# VoltageHeaders.net
KiCad netlist of a schematic drawn in Altium Designer
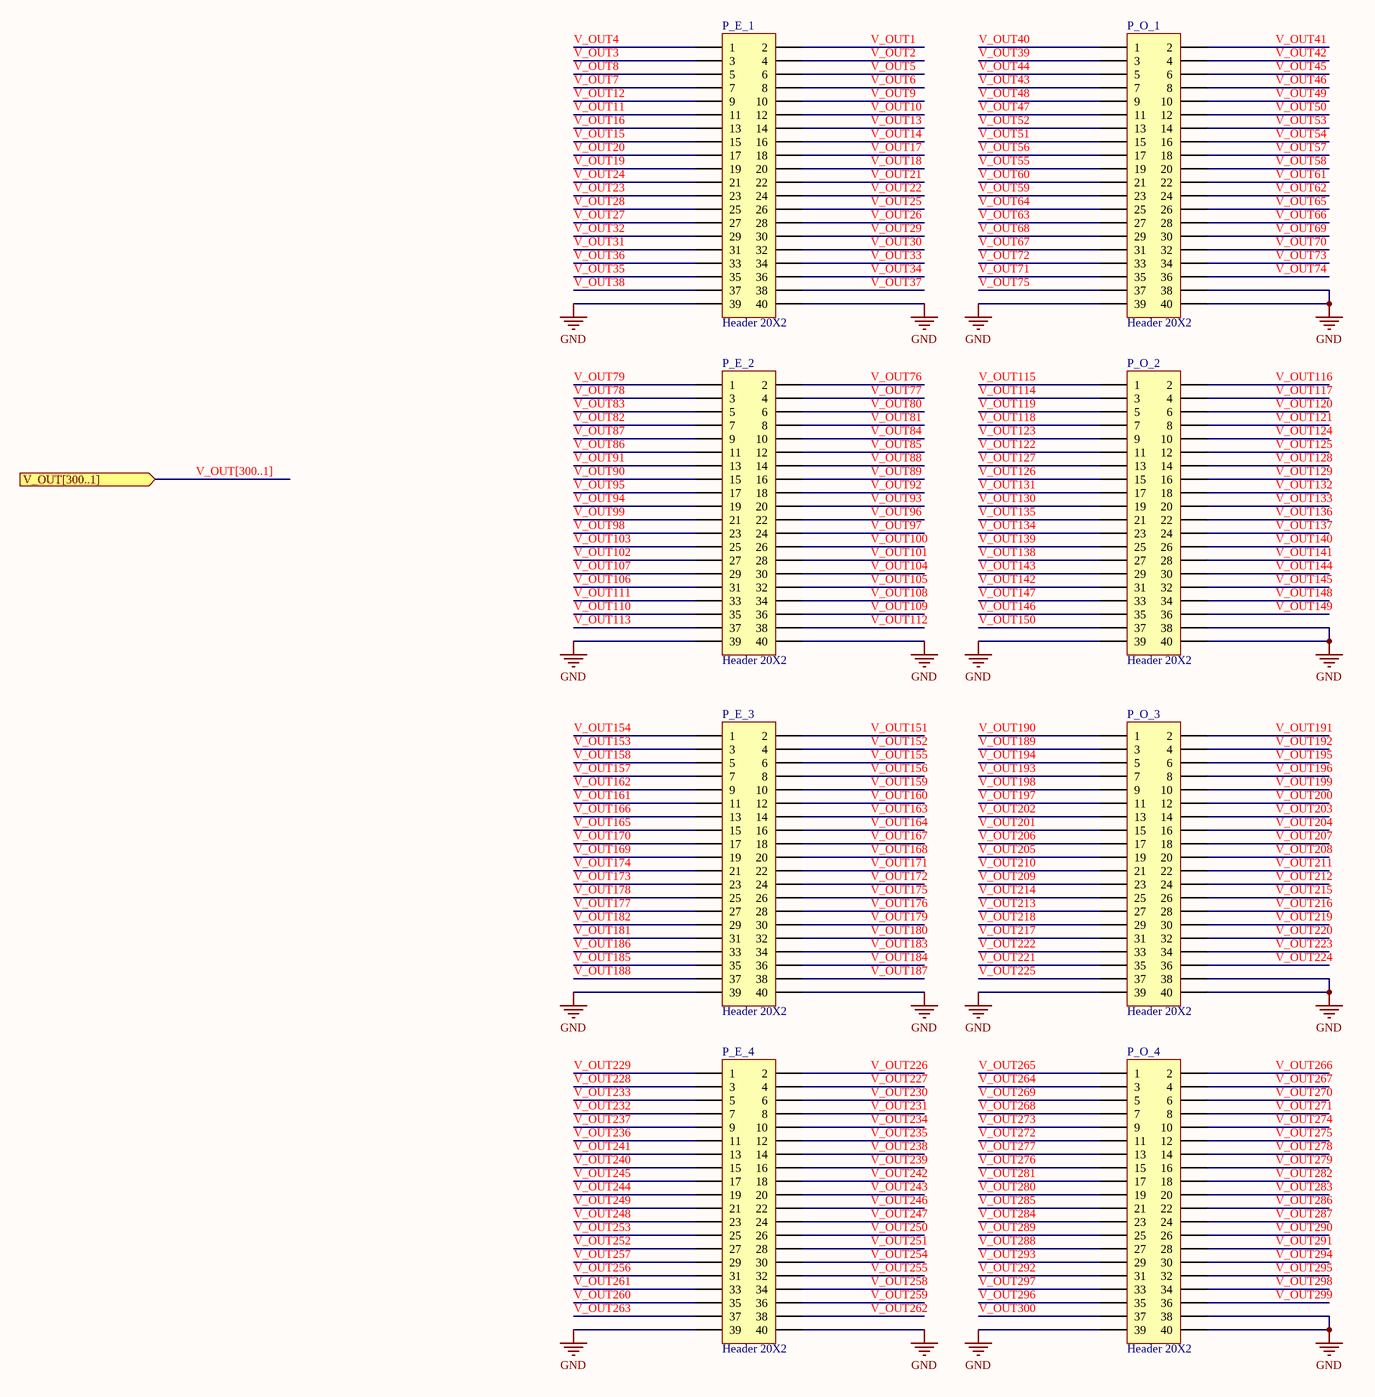
[diagram p0: VoltageHeaders.SchDoc]

(export (version "E")
  (design (tool "Eeschema 10.0.6"))
  (components
    (comp (ref "P_E_1")
      (value "Header 20X2")
      (footprint "HDR2X20")
      (description "Headers & Wire Housings 2X20 POS VERT TIN")
      (fields (field (name "MFR") "TE Connectivity / AMP") (field (name "MFR PART NO") "2-826942-0"))
      (libsource (lib "Miscellaneous Connectors") (part "Header 20X2"))
    )
    (comp (ref "P_E_2")
      (value "Header 20X2")
      (footprint "HDR2X20")
      (description "Headers & Wire Housings 2X20 POS VERT TIN")
      (fields (field (name "MFR") "TE Connectivity / AMP") (field (name "MFR PART NO") "2-826942-0"))
      (libsource (lib "Miscellaneous Connectors") (part "Header 20X2"))
    )
    (comp (ref "P_E_3")
      (value "Header 20X2")
      (footprint "HDR2X20")
      (description "Headers & Wire Housings 2X20 POS VERT TIN")
      (fields (field (name "MFR") "TE Connectivity / AMP") (field (name "MFR PART NO") "2-826942-0"))
      (libsource (lib "Miscellaneous Connectors") (part "Header 20X2"))
    )
    (comp (ref "P_E_4")
      (value "Header 20X2")
      (footprint "HDR2X20")
      (description "Headers & Wire Housings 2X20 POS VERT TIN")
      (fields (field (name "MFR") "TE Connectivity / AMP") (field (name "MFR PART NO") "2-826942-0"))
      (libsource (lib "Miscellaneous Connectors") (part "Header 20X2"))
    )
    (comp (ref "P_O_1")
      (value "Header 20X2")
      (footprint "HDR2X20")
      (description "Headers & Wire Housings 2X20 POS VERT TIN")
      (fields (field (name "MFR") "TE Connectivity / AMP") (field (name "MFR PART NO") "2-826942-0"))
      (libsource (lib "Miscellaneous Connectors") (part "Header 20X2"))
    )
    (comp (ref "P_O_2")
      (value "Header 20X2")
      (footprint "HDR2X20")
      (description "Headers & Wire Housings 2X20 POS VERT TIN")
      (fields (field (name "MFR") "TE Connectivity / AMP") (field (name "MFR PART NO") "2-826942-0"))
      (libsource (lib "Miscellaneous Connectors") (part "Header 20X2"))
    )
    (comp (ref "P_O_3")
      (value "Header 20X2")
      (footprint "HDR2X20")
      (description "Headers & Wire Housings 2X20 POS VERT TIN")
      (fields (field (name "MFR") "TE Connectivity / AMP") (field (name "MFR PART NO") "2-826942-0"))
      (libsource (lib "Miscellaneous Connectors") (part "Header 20X2"))
    )
    (comp (ref "P_O_4")
      (value "Header 20X2")
      (footprint "HDR2X20")
      (description "Headers & Wire Housings 2X20 POS VERT TIN")
      (fields (field (name "MFR") "TE Connectivity / AMP") (field (name "MFR PART NO") "2-826942-0"))
      (libsource (lib "Miscellaneous Connectors") (part "Header 20X2"))
    )
  )
  (nets
    (net (code "1") (name "/V_OUT1") (class "Default")
      (node (ref "P_E_1") (pin "2") (pinfunction "2_2") (pintype "passive"))
    )
    (net (code "2") (name "/V_OUT2") (class "Default")
      (node (ref "P_E_1") (pin "4") (pinfunction "4_4") (pintype "passive"))
    )
    (net (code "3") (name "/V_OUT3") (class "Default")
      (node (ref "P_E_1") (pin "3") (pinfunction "3_3") (pintype "passive"))
    )
    (net (code "4") (name "/V_OUT4") (class "Default")
      (node (ref "P_E_1") (pin "1") (pinfunction "1_1") (pintype "passive"))
    )
    (net (code "5") (name "/V_OUT5") (class "Default")
      (node (ref "P_E_1") (pin "6") (pinfunction "6_6") (pintype "passive"))
    )
    (net (code "6") (name "/V_OUT6") (class "Default")
      (node (ref "P_E_1") (pin "8") (pinfunction "8_8") (pintype "passive"))
    )
    (net (code "7") (name "/V_OUT7") (class "Default")
      (node (ref "P_E_1") (pin "7") (pinfunction "7_7") (pintype "passive"))
    )
    (net (code "8") (name "/V_OUT8") (class "Default")
      (node (ref "P_E_1") (pin "5") (pinfunction "5_5") (pintype "passive"))
    )
    (net (code "9") (name "/V_OUT9") (class "Default")
      (node (ref "P_E_1") (pin "10") (pinfunction "10_10") (pintype "passive"))
    )
    (net (code "10") (name "/V_OUT10") (class "Default")
      (node (ref "P_E_1") (pin "12") (pinfunction "12_12") (pintype "passive"))
    )
    (net (code "11") (name "/V_OUT11") (class "Default")
      (node (ref "P_E_1") (pin "11") (pinfunction "11_11") (pintype "passive"))
    )
    (net (code "12") (name "/V_OUT12") (class "Default")
      (node (ref "P_E_1") (pin "9") (pinfunction "9_9") (pintype "passive"))
    )
    (net (code "13") (name "/V_OUT13") (class "Default")
      (node (ref "P_E_1") (pin "14") (pinfunction "14_14") (pintype "passive"))
    )
    (net (code "14") (name "/V_OUT14") (class "Default")
      (node (ref "P_E_1") (pin "16") (pinfunction "16_16") (pintype "passive"))
    )
    (net (code "15") (name "/V_OUT15") (class "Default")
      (node (ref "P_E_1") (pin "15") (pinfunction "15_15") (pintype "passive"))
    )
    (net (code "16") (name "/V_OUT16") (class "Default")
      (node (ref "P_E_1") (pin "13") (pinfunction "13_13") (pintype "passive"))
    )
    (net (code "17") (name "/V_OUT17") (class "Default")
      (node (ref "P_E_1") (pin "18") (pinfunction "18_18") (pintype "passive"))
    )
    (net (code "18") (name "/V_OUT18") (class "Default")
      (node (ref "P_E_1") (pin "20") (pinfunction "20_20") (pintype "passive"))
    )
    (net (code "19") (name "/V_OUT19") (class "Default")
      (node (ref "P_E_1") (pin "19") (pinfunction "19_19") (pintype "passive"))
    )
    (net (code "20") (name "/V_OUT20") (class "Default")
      (node (ref "P_E_1") (pin "17") (pinfunction "17_17") (pintype "passive"))
    )
    (net (code "21") (name "/V_OUT21") (class "Default")
      (node (ref "P_E_1") (pin "22") (pinfunction "22_22") (pintype "passive"))
    )
    (net (code "22") (name "/V_OUT22") (class "Default")
      (node (ref "P_E_1") (pin "24") (pinfunction "24_24") (pintype "passive"))
    )
    (net (code "23") (name "/V_OUT23") (class "Default")
      (node (ref "P_E_1") (pin "23") (pinfunction "23_23") (pintype "passive"))
    )
    (net (code "24") (name "/V_OUT24") (class "Default")
      (node (ref "P_E_1") (pin "21") (pinfunction "21_21") (pintype "passive"))
    )
    (net (code "25") (name "/V_OUT25") (class "Default")
      (node (ref "P_E_1") (pin "26") (pinfunction "26_26") (pintype "passive"))
    )
    (net (code "26") (name "/V_OUT26") (class "Default")
      (node (ref "P_E_1") (pin "28") (pinfunction "28_28") (pintype "passive"))
    )
    (net (code "27") (name "/V_OUT27") (class "Default")
      (node (ref "P_E_1") (pin "27") (pinfunction "27_27") (pintype "passive"))
    )
    (net (code "28") (name "/V_OUT28") (class "Default")
      (node (ref "P_E_1") (pin "25") (pinfunction "25_25") (pintype "passive"))
    )
    (net (code "29") (name "/V_OUT29") (class "Default")
      (node (ref "P_E_1") (pin "30") (pinfunction "30_30") (pintype "passive"))
    )
    (net (code "30") (name "/V_OUT30") (class "Default")
      (node (ref "P_E_1") (pin "32") (pinfunction "32_32") (pintype "passive"))
    )
    (net (code "31") (name "/V_OUT31") (class "Default")
      (node (ref "P_E_1") (pin "31") (pinfunction "31_31") (pintype "passive"))
    )
    (net (code "32") (name "/V_OUT32") (class "Default")
      (node (ref "P_E_1") (pin "29") (pinfunction "29_29") (pintype "passive"))
    )
    (net (code "33") (name "/V_OUT33") (class "Default")
      (node (ref "P_E_1") (pin "34") (pinfunction "34_34") (pintype "passive"))
    )
    (net (code "34") (name "/V_OUT34") (class "Default")
      (node (ref "P_E_1") (pin "36") (pinfunction "36_36") (pintype "passive"))
    )
    (net (code "35") (name "/V_OUT35") (class "Default")
      (node (ref "P_E_1") (pin "35") (pinfunction "35_35") (pintype "passive"))
    )
    (net (code "36") (name "/V_OUT36") (class "Default")
      (node (ref "P_E_1") (pin "33") (pinfunction "33_33") (pintype "passive"))
    )
    (net (code "37") (name "/V_OUT37") (class "Default")
      (node (ref "P_E_1") (pin "38") (pinfunction "38_38") (pintype "passive"))
    )
    (net (code "38") (name "/V_OUT38") (class "Default")
      (node (ref "P_E_1") (pin "37") (pinfunction "37_37") (pintype "passive"))
    )
    (net (code "39") (name "/V_OUT39") (class "Default")
      (node (ref "P_O_1") (pin "3") (pinfunction "3_3") (pintype "passive"))
    )
    (net (code "40") (name "/V_OUT40") (class "Default")
      (node (ref "P_O_1") (pin "1") (pinfunction "1_1") (pintype "passive"))
    )
    (net (code "41") (name "/V_OUT41") (class "Default")
      (node (ref "P_O_1") (pin "2") (pinfunction "2_2") (pintype "passive"))
    )
    (net (code "42") (name "/V_OUT42") (class "Default")
      (node (ref "P_O_1") (pin "4") (pinfunction "4_4") (pintype "passive"))
    )
    (net (code "43") (name "/V_OUT43") (class "Default")
      (node (ref "P_O_1") (pin "7") (pinfunction "7_7") (pintype "passive"))
    )
    (net (code "44") (name "/V_OUT44") (class "Default")
      (node (ref "P_O_1") (pin "5") (pinfunction "5_5") (pintype "passive"))
    )
    (net (code "45") (name "/V_OUT45") (class "Default")
      (node (ref "P_O_1") (pin "6") (pinfunction "6_6") (pintype "passive"))
    )
    (net (code "46") (name "/V_OUT46") (class "Default")
      (node (ref "P_O_1") (pin "8") (pinfunction "8_8") (pintype "passive"))
    )
    (net (code "47") (name "/V_OUT47") (class "Default")
      (node (ref "P_O_1") (pin "11") (pinfunction "11_11") (pintype "passive"))
    )
    (net (code "48") (name "/V_OUT48") (class "Default")
      (node (ref "P_O_1") (pin "9") (pinfunction "9_9") (pintype "passive"))
    )
    (net (code "49") (name "/V_OUT49") (class "Default")
      (node (ref "P_O_1") (pin "10") (pinfunction "10_10") (pintype "passive"))
    )
    (net (code "50") (name "/V_OUT50") (class "Default")
      (node (ref "P_O_1") (pin "12") (pinfunction "12_12") (pintype "passive"))
    )
    (net (code "51") (name "/V_OUT51") (class "Default")
      (node (ref "P_O_1") (pin "15") (pinfunction "15_15") (pintype "passive"))
    )
    (net (code "52") (name "/V_OUT52") (class "Default")
      (node (ref "P_O_1") (pin "13") (pinfunction "13_13") (pintype "passive"))
    )
    (net (code "53") (name "/V_OUT53") (class "Default")
      (node (ref "P_O_1") (pin "14") (pinfunction "14_14") (pintype "passive"))
    )
    (net (code "54") (name "/V_OUT54") (class "Default")
      (node (ref "P_O_1") (pin "16") (pinfunction "16_16") (pintype "passive"))
    )
    (net (code "55") (name "/V_OUT55") (class "Default")
      (node (ref "P_O_1") (pin "19") (pinfunction "19_19") (pintype "passive"))
    )
    (net (code "56") (name "/V_OUT56") (class "Default")
      (node (ref "P_O_1") (pin "17") (pinfunction "17_17") (pintype "passive"))
    )
    (net (code "57") (name "/V_OUT57") (class "Default")
      (node (ref "P_O_1") (pin "18") (pinfunction "18_18") (pintype "passive"))
    )
    (net (code "58") (name "/V_OUT58") (class "Default")
      (node (ref "P_O_1") (pin "20") (pinfunction "20_20") (pintype "passive"))
    )
    (net (code "59") (name "/V_OUT59") (class "Default")
      (node (ref "P_O_1") (pin "23") (pinfunction "23_23") (pintype "passive"))
    )
    (net (code "60") (name "/V_OUT60") (class "Default")
      (node (ref "P_O_1") (pin "21") (pinfunction "21_21") (pintype "passive"))
    )
    (net (code "61") (name "/V_OUT61") (class "Default")
      (node (ref "P_O_1") (pin "22") (pinfunction "22_22") (pintype "passive"))
    )
    (net (code "62") (name "/V_OUT62") (class "Default")
      (node (ref "P_O_1") (pin "24") (pinfunction "24_24") (pintype "passive"))
    )
    (net (code "63") (name "/V_OUT63") (class "Default")
      (node (ref "P_O_1") (pin "27") (pinfunction "27_27") (pintype "passive"))
    )
    (net (code "64") (name "/V_OUT64") (class "Default")
      (node (ref "P_O_1") (pin "25") (pinfunction "25_25") (pintype "passive"))
    )
    (net (code "65") (name "/V_OUT65") (class "Default")
      (node (ref "P_O_1") (pin "26") (pinfunction "26_26") (pintype "passive"))
    )
    (net (code "66") (name "/V_OUT66") (class "Default")
      (node (ref "P_O_1") (pin "28") (pinfunction "28_28") (pintype "passive"))
    )
    (net (code "67") (name "/V_OUT67") (class "Default")
      (node (ref "P_O_1") (pin "31") (pinfunction "31_31") (pintype "passive"))
    )
    (net (code "68") (name "/V_OUT68") (class "Default")
      (node (ref "P_O_1") (pin "29") (pinfunction "29_29") (pintype "passive"))
    )
    (net (code "69") (name "/V_OUT69") (class "Default")
      (node (ref "P_O_1") (pin "30") (pinfunction "30_30") (pintype "passive"))
    )
    (net (code "70") (name "/V_OUT70") (class "Default")
      (node (ref "P_O_1") (pin "32") (pinfunction "32_32") (pintype "passive"))
    )
    (net (code "71") (name "/V_OUT71") (class "Default")
      (node (ref "P_O_1") (pin "35") (pinfunction "35_35") (pintype "passive"))
    )
    (net (code "72") (name "/V_OUT72") (class "Default")
      (node (ref "P_O_1") (pin "33") (pinfunction "33_33") (pintype "passive"))
    )
    (net (code "73") (name "/V_OUT73") (class "Default")
      (node (ref "P_O_1") (pin "34") (pinfunction "34_34") (pintype "passive"))
    )
    (net (code "74") (name "/V_OUT74") (class "Default")
      (node (ref "P_O_1") (pin "36") (pinfunction "36_36") (pintype "passive"))
    )
    (net (code "75") (name "/V_OUT75") (class "Default")
      (node (ref "P_O_1") (pin "37") (pinfunction "37_37") (pintype "passive"))
    )
    (net (code "76") (name "/V_OUT76") (class "Default")
      (node (ref "P_E_2") (pin "2") (pinfunction "2_2") (pintype "passive"))
    )
    (net (code "77") (name "/V_OUT77") (class "Default")
      (node (ref "P_E_2") (pin "4") (pinfunction "4_4") (pintype "passive"))
    )
    (net (code "78") (name "/V_OUT78") (class "Default")
      (node (ref "P_E_2") (pin "3") (pinfunction "3_3") (pintype "passive"))
    )
    (net (code "79") (name "/V_OUT79") (class "Default")
      (node (ref "P_E_2") (pin "1") (pinfunction "1_1") (pintype "passive"))
    )
    (net (code "80") (name "/V_OUT80") (class "Default")
      (node (ref "P_E_2") (pin "6") (pinfunction "6_6") (pintype "passive"))
    )
    (net (code "81") (name "/V_OUT81") (class "Default")
      (node (ref "P_E_2") (pin "8") (pinfunction "8_8") (pintype "passive"))
    )
    (net (code "82") (name "/V_OUT82") (class "Default")
      (node (ref "P_E_2") (pin "7") (pinfunction "7_7") (pintype "passive"))
    )
    (net (code "83") (name "/V_OUT83") (class "Default")
      (node (ref "P_E_2") (pin "5") (pinfunction "5_5") (pintype "passive"))
    )
    (net (code "84") (name "/V_OUT84") (class "Default")
      (node (ref "P_E_2") (pin "10") (pinfunction "10_10") (pintype "passive"))
    )
    (net (code "85") (name "/V_OUT85") (class "Default")
      (node (ref "P_E_2") (pin "12") (pinfunction "12_12") (pintype "passive"))
    )
    (net (code "86") (name "/V_OUT86") (class "Default")
      (node (ref "P_E_2") (pin "11") (pinfunction "11_11") (pintype "passive"))
    )
    (net (code "87") (name "/V_OUT87") (class "Default")
      (node (ref "P_E_2") (pin "9") (pinfunction "9_9") (pintype "passive"))
    )
    (net (code "88") (name "/V_OUT88") (class "Default")
      (node (ref "P_E_2") (pin "14") (pinfunction "14_14") (pintype "passive"))
    )
    (net (code "89") (name "/V_OUT89") (class "Default")
      (node (ref "P_E_2") (pin "16") (pinfunction "16_16") (pintype "passive"))
    )
    (net (code "90") (name "/V_OUT90") (class "Default")
      (node (ref "P_E_2") (pin "15") (pinfunction "15_15") (pintype "passive"))
    )
    (net (code "91") (name "/V_OUT91") (class "Default")
      (node (ref "P_E_2") (pin "13") (pinfunction "13_13") (pintype "passive"))
    )
    (net (code "92") (name "/V_OUT92") (class "Default")
      (node (ref "P_E_2") (pin "18") (pinfunction "18_18") (pintype "passive"))
    )
    (net (code "93") (name "/V_OUT93") (class "Default")
      (node (ref "P_E_2") (pin "20") (pinfunction "20_20") (pintype "passive"))
    )
    (net (code "94") (name "/V_OUT94") (class "Default")
      (node (ref "P_E_2") (pin "19") (pinfunction "19_19") (pintype "passive"))
    )
    (net (code "95") (name "/V_OUT95") (class "Default")
      (node (ref "P_E_2") (pin "17") (pinfunction "17_17") (pintype "passive"))
    )
    (net (code "96") (name "/V_OUT96") (class "Default")
      (node (ref "P_E_2") (pin "22") (pinfunction "22_22") (pintype "passive"))
    )
    (net (code "97") (name "/V_OUT97") (class "Default")
      (node (ref "P_E_2") (pin "24") (pinfunction "24_24") (pintype "passive"))
    )
    (net (code "98") (name "/V_OUT98") (class "Default")
      (node (ref "P_E_2") (pin "23") (pinfunction "23_23") (pintype "passive"))
    )
    (net (code "99") (name "/V_OUT99") (class "Default")
      (node (ref "P_E_2") (pin "21") (pinfunction "21_21") (pintype "passive"))
    )
    (net (code "100") (name "/V_OUT100") (class "Default")
      (node (ref "P_E_2") (pin "26") (pinfunction "26_26") (pintype "passive"))
    )
    (net (code "101") (name "/V_OUT101") (class "Default")
      (node (ref "P_E_2") (pin "28") (pinfunction "28_28") (pintype "passive"))
    )
    (net (code "102") (name "/V_OUT102") (class "Default")
      (node (ref "P_E_2") (pin "27") (pinfunction "27_27") (pintype "passive"))
    )
    (net (code "103") (name "/V_OUT103") (class "Default")
      (node (ref "P_E_2") (pin "25") (pinfunction "25_25") (pintype "passive"))
    )
    (net (code "104") (name "/V_OUT104") (class "Default")
      (node (ref "P_E_2") (pin "30") (pinfunction "30_30") (pintype "passive"))
    )
    (net (code "105") (name "/V_OUT105") (class "Default")
      (node (ref "P_E_2") (pin "32") (pinfunction "32_32") (pintype "passive"))
    )
    (net (code "106") (name "/V_OUT106") (class "Default")
      (node (ref "P_E_2") (pin "31") (pinfunction "31_31") (pintype "passive"))
    )
    (net (code "107") (name "/V_OUT107") (class "Default")
      (node (ref "P_E_2") (pin "29") (pinfunction "29_29") (pintype "passive"))
    )
    (net (code "108") (name "/V_OUT108") (class "Default")
      (node (ref "P_E_2") (pin "34") (pinfunction "34_34") (pintype "passive"))
    )
    (net (code "109") (name "/V_OUT109") (class "Default")
      (node (ref "P_E_2") (pin "36") (pinfunction "36_36") (pintype "passive"))
    )
    (net (code "110") (name "/V_OUT110") (class "Default")
      (node (ref "P_E_2") (pin "35") (pinfunction "35_35") (pintype "passive"))
    )
    (net (code "111") (name "/V_OUT111") (class "Default")
      (node (ref "P_E_2") (pin "33") (pinfunction "33_33") (pintype "passive"))
    )
    (net (code "112") (name "/V_OUT112") (class "Default")
      (node (ref "P_E_2") (pin "38") (pinfunction "38_38") (pintype "passive"))
    )
    (net (code "113") (name "/V_OUT113") (class "Default")
      (node (ref "P_E_2") (pin "37") (pinfunction "37_37") (pintype "passive"))
    )
    (net (code "114") (name "/V_OUT114") (class "Default")
      (node (ref "P_O_2") (pin "3") (pinfunction "3_3") (pintype "passive"))
    )
    (net (code "115") (name "/V_OUT115") (class "Default")
      (node (ref "P_O_2") (pin "1") (pinfunction "1_1") (pintype "passive"))
    )
    (net (code "116") (name "/V_OUT116") (class "Default")
      (node (ref "P_O_2") (pin "2") (pinfunction "2_2") (pintype "passive"))
    )
    (net (code "117") (name "/V_OUT117") (class "Default")
      (node (ref "P_O_2") (pin "4") (pinfunction "4_4") (pintype "passive"))
    )
    (net (code "118") (name "/V_OUT118") (class "Default")
      (node (ref "P_O_2") (pin "7") (pinfunction "7_7") (pintype "passive"))
    )
    (net (code "119") (name "/V_OUT119") (class "Default")
      (node (ref "P_O_2") (pin "5") (pinfunction "5_5") (pintype "passive"))
    )
    (net (code "120") (name "/V_OUT120") (class "Default")
      (node (ref "P_O_2") (pin "6") (pinfunction "6_6") (pintype "passive"))
    )
    (net (code "121") (name "/V_OUT121") (class "Default")
      (node (ref "P_O_2") (pin "8") (pinfunction "8_8") (pintype "passive"))
    )
    (net (code "122") (name "/V_OUT122") (class "Default")
      (node (ref "P_O_2") (pin "11") (pinfunction "11_11") (pintype "passive"))
    )
    (net (code "123") (name "/V_OUT123") (class "Default")
      (node (ref "P_O_2") (pin "9") (pinfunction "9_9") (pintype "passive"))
    )
    (net (code "124") (name "/V_OUT124") (class "Default")
      (node (ref "P_O_2") (pin "10") (pinfunction "10_10") (pintype "passive"))
    )
    (net (code "125") (name "/V_OUT125") (class "Default")
      (node (ref "P_O_2") (pin "12") (pinfunction "12_12") (pintype "passive"))
    )
    (net (code "126") (name "/V_OUT126") (class "Default")
      (node (ref "P_O_2") (pin "15") (pinfunction "15_15") (pintype "passive"))
    )
    (net (code "127") (name "/V_OUT127") (class "Default")
      (node (ref "P_O_2") (pin "13") (pinfunction "13_13") (pintype "passive"))
    )
    (net (code "128") (name "/V_OUT128") (class "Default")
      (node (ref "P_O_2") (pin "14") (pinfunction "14_14") (pintype "passive"))
    )
    (net (code "129") (name "/V_OUT129") (class "Default")
      (node (ref "P_O_2") (pin "16") (pinfunction "16_16") (pintype "passive"))
    )
    (net (code "130") (name "/V_OUT130") (class "Default")
      (node (ref "P_O_2") (pin "19") (pinfunction "19_19") (pintype "passive"))
    )
    (net (code "131") (name "/V_OUT131") (class "Default")
      (node (ref "P_O_2") (pin "17") (pinfunction "17_17") (pintype "passive"))
    )
    (net (code "132") (name "/V_OUT132") (class "Default")
      (node (ref "P_O_2") (pin "18") (pinfunction "18_18") (pintype "passive"))
    )
    (net (code "133") (name "/V_OUT133") (class "Default")
      (node (ref "P_O_2") (pin "20") (pinfunction "20_20") (pintype "passive"))
    )
    (net (code "134") (name "/V_OUT134") (class "Default")
      (node (ref "P_O_2") (pin "23") (pinfunction "23_23") (pintype "passive"))
    )
    (net (code "135") (name "/V_OUT135") (class "Default")
      (node (ref "P_O_2") (pin "21") (pinfunction "21_21") (pintype "passive"))
    )
    (net (code "136") (name "/V_OUT136") (class "Default")
      (node (ref "P_O_2") (pin "22") (pinfunction "22_22") (pintype "passive"))
    )
    (net (code "137") (name "/V_OUT137") (class "Default")
      (node (ref "P_O_2") (pin "24") (pinfunction "24_24") (pintype "passive"))
    )
    (net (code "138") (name "/V_OUT138") (class "Default")
      (node (ref "P_O_2") (pin "27") (pinfunction "27_27") (pintype "passive"))
    )
    (net (code "139") (name "/V_OUT139") (class "Default")
      (node (ref "P_O_2") (pin "25") (pinfunction "25_25") (pintype "passive"))
    )
    (net (code "140") (name "/V_OUT140") (class "Default")
      (node (ref "P_O_2") (pin "26") (pinfunction "26_26") (pintype "passive"))
    )
    (net (code "141") (name "/V_OUT141") (class "Default")
      (node (ref "P_O_2") (pin "28") (pinfunction "28_28") (pintype "passive"))
    )
    (net (code "142") (name "/V_OUT142") (class "Default")
      (node (ref "P_O_2") (pin "31") (pinfunction "31_31") (pintype "passive"))
    )
    (net (code "143") (name "/V_OUT143") (class "Default")
      (node (ref "P_O_2") (pin "29") (pinfunction "29_29") (pintype "passive"))
    )
    (net (code "144") (name "/V_OUT144") (class "Default")
      (node (ref "P_O_2") (pin "30") (pinfunction "30_30") (pintype "passive"))
    )
    (net (code "145") (name "/V_OUT145") (class "Default")
      (node (ref "P_O_2") (pin "32") (pinfunction "32_32") (pintype "passive"))
    )
    (net (code "146") (name "/V_OUT146") (class "Default")
      (node (ref "P_O_2") (pin "35") (pinfunction "35_35") (pintype "passive"))
    )
    (net (code "147") (name "/V_OUT147") (class "Default")
      (node (ref "P_O_2") (pin "33") (pinfunction "33_33") (pintype "passive"))
    )
    (net (code "148") (name "/V_OUT148") (class "Default")
      (node (ref "P_O_2") (pin "34") (pinfunction "34_34") (pintype "passive"))
    )
    (net (code "149") (name "/V_OUT149") (class "Default")
      (node (ref "P_O_2") (pin "36") (pinfunction "36_36") (pintype "passive"))
    )
    (net (code "150") (name "/V_OUT150") (class "Default")
      (node (ref "P_O_2") (pin "37") (pinfunction "37_37") (pintype "passive"))
    )
    (net (code "151") (name "/V_OUT151") (class "Default")
      (node (ref "P_E_3") (pin "2") (pinfunction "2_2") (pintype "passive"))
    )
    (net (code "152") (name "/V_OUT152") (class "Default")
      (node (ref "P_E_3") (pin "4") (pinfunction "4_4") (pintype "passive"))
    )
    (net (code "153") (name "/V_OUT153") (class "Default")
      (node (ref "P_E_3") (pin "3") (pinfunction "3_3") (pintype "passive"))
    )
    (net (code "154") (name "/V_OUT154") (class "Default")
      (node (ref "P_E_3") (pin "1") (pinfunction "1_1") (pintype "passive"))
    )
    (net (code "155") (name "/V_OUT155") (class "Default")
      (node (ref "P_E_3") (pin "6") (pinfunction "6_6") (pintype "passive"))
    )
    (net (code "156") (name "/V_OUT156") (class "Default")
      (node (ref "P_E_3") (pin "8") (pinfunction "8_8") (pintype "passive"))
    )
    (net (code "157") (name "/V_OUT157") (class "Default")
      (node (ref "P_E_3") (pin "7") (pinfunction "7_7") (pintype "passive"))
    )
    (net (code "158") (name "/V_OUT158") (class "Default")
      (node (ref "P_E_3") (pin "5") (pinfunction "5_5") (pintype "passive"))
    )
    (net (code "159") (name "/V_OUT159") (class "Default")
      (node (ref "P_E_3") (pin "10") (pinfunction "10_10") (pintype "passive"))
    )
    (net (code "160") (name "/V_OUT160") (class "Default")
      (node (ref "P_E_3") (pin "12") (pinfunction "12_12") (pintype "passive"))
    )
    (net (code "161") (name "/V_OUT161") (class "Default")
      (node (ref "P_E_3") (pin "11") (pinfunction "11_11") (pintype "passive"))
    )
    (net (code "162") (name "/V_OUT162") (class "Default")
      (node (ref "P_E_3") (pin "9") (pinfunction "9_9") (pintype "passive"))
    )
    (net (code "163") (name "/V_OUT163") (class "Default")
      (node (ref "P_E_3") (pin "14") (pinfunction "14_14") (pintype "passive"))
    )
    (net (code "164") (name "/V_OUT164") (class "Default")
      (node (ref "P_E_3") (pin "16") (pinfunction "16_16") (pintype "passive"))
    )
    (net (code "165") (name "/V_OUT165") (class "Default")
      (node (ref "P_E_3") (pin "15") (pinfunction "15_15") (pintype "passive"))
    )
    (net (code "166") (name "/V_OUT166") (class "Default")
      (node (ref "P_E_3") (pin "13") (pinfunction "13_13") (pintype "passive"))
    )
    (net (code "167") (name "/V_OUT167") (class "Default")
      (node (ref "P_E_3") (pin "18") (pinfunction "18_18") (pintype "passive"))
    )
    (net (code "168") (name "/V_OUT168") (class "Default")
      (node (ref "P_E_3") (pin "20") (pinfunction "20_20") (pintype "passive"))
    )
    (net (code "169") (name "/V_OUT169") (class "Default")
      (node (ref "P_E_3") (pin "19") (pinfunction "19_19") (pintype "passive"))
    )
    (net (code "170") (name "/V_OUT170") (class "Default")
      (node (ref "P_E_3") (pin "17") (pinfunction "17_17") (pintype "passive"))
    )
    (net (code "171") (name "/V_OUT171") (class "Default")
      (node (ref "P_E_3") (pin "22") (pinfunction "22_22") (pintype "passive"))
    )
    (net (code "172") (name "/V_OUT172") (class "Default")
      (node (ref "P_E_3") (pin "24") (pinfunction "24_24") (pintype "passive"))
    )
    (net (code "173") (name "/V_OUT173") (class "Default")
      (node (ref "P_E_3") (pin "23") (pinfunction "23_23") (pintype "passive"))
    )
    (net (code "174") (name "/V_OUT174") (class "Default")
      (node (ref "P_E_3") (pin "21") (pinfunction "21_21") (pintype "passive"))
    )
    (net (code "175") (name "/V_OUT175") (class "Default")
      (node (ref "P_E_3") (pin "26") (pinfunction "26_26") (pintype "passive"))
    )
    (net (code "176") (name "/V_OUT176") (class "Default")
      (node (ref "P_E_3") (pin "28") (pinfunction "28_28") (pintype "passive"))
    )
    (net (code "177") (name "/V_OUT177") (class "Default")
      (node (ref "P_E_3") (pin "27") (pinfunction "27_27") (pintype "passive"))
    )
    (net (code "178") (name "/V_OUT178") (class "Default")
      (node (ref "P_E_3") (pin "25") (pinfunction "25_25") (pintype "passive"))
    )
    (net (code "179") (name "/V_OUT179") (class "Default")
      (node (ref "P_E_3") (pin "30") (pinfunction "30_30") (pintype "passive"))
    )
    (net (code "180") (name "/V_OUT180") (class "Default")
      (node (ref "P_E_3") (pin "32") (pinfunction "32_32") (pintype "passive"))
    )
    (net (code "181") (name "/V_OUT181") (class "Default")
      (node (ref "P_E_3") (pin "31") (pinfunction "31_31") (pintype "passive"))
    )
    (net (code "182") (name "/V_OUT182") (class "Default")
      (node (ref "P_E_3") (pin "29") (pinfunction "29_29") (pintype "passive"))
    )
    (net (code "183") (name "/V_OUT183") (class "Default")
      (node (ref "P_E_3") (pin "34") (pinfunction "34_34") (pintype "passive"))
    )
    (net (code "184") (name "/V_OUT184") (class "Default")
      (node (ref "P_E_3") (pin "36") (pinfunction "36_36") (pintype "passive"))
    )
    (net (code "185") (name "/V_OUT185") (class "Default")
      (node (ref "P_E_3") (pin "35") (pinfunction "35_35") (pintype "passive"))
    )
    (net (code "186") (name "/V_OUT186") (class "Default")
      (node (ref "P_E_3") (pin "33") (pinfunction "33_33") (pintype "passive"))
    )
    (net (code "187") (name "/V_OUT187") (class "Default")
      (node (ref "P_E_3") (pin "38") (pinfunction "38_38") (pintype "passive"))
    )
    (net (code "188") (name "/V_OUT188") (class "Default")
      (node (ref "P_E_3") (pin "37") (pinfunction "37_37") (pintype "passive"))
    )
    (net (code "189") (name "/V_OUT189") (class "Default")
      (node (ref "P_O_3") (pin "3") (pinfunction "3_3") (pintype "passive"))
    )
    (net (code "190") (name "/V_OUT190") (class "Default")
      (node (ref "P_O_3") (pin "1") (pinfunction "1_1") (pintype "passive"))
    )
    (net (code "191") (name "/V_OUT191") (class "Default")
      (node (ref "P_O_3") (pin "2") (pinfunction "2_2") (pintype "passive"))
    )
    (net (code "192") (name "/V_OUT192") (class "Default")
      (node (ref "P_O_3") (pin "4") (pinfunction "4_4") (pintype "passive"))
    )
    (net (code "193") (name "/V_OUT193") (class "Default")
      (node (ref "P_O_3") (pin "7") (pinfunction "7_7") (pintype "passive"))
    )
    (net (code "194") (name "/V_OUT194") (class "Default")
      (node (ref "P_O_3") (pin "5") (pinfunction "5_5") (pintype "passive"))
    )
    (net (code "195") (name "/V_OUT195") (class "Default")
      (node (ref "P_O_3") (pin "6") (pinfunction "6_6") (pintype "passive"))
    )
    (net (code "196") (name "/V_OUT196") (class "Default")
      (node (ref "P_O_3") (pin "8") (pinfunction "8_8") (pintype "passive"))
    )
    (net (code "197") (name "/V_OUT197") (class "Default")
      (node (ref "P_O_3") (pin "11") (pinfunction "11_11") (pintype "passive"))
    )
    (net (code "198") (name "/V_OUT198") (class "Default")
      (node (ref "P_O_3") (pin "9") (pinfunction "9_9") (pintype "passive"))
    )
    (net (code "199") (name "/V_OUT199") (class "Default")
      (node (ref "P_O_3") (pin "10") (pinfunction "10_10") (pintype "passive"))
    )
    (net (code "200") (name "/V_OUT200") (class "Default")
      (node (ref "P_O_3") (pin "12") (pinfunction "12_12") (pintype "passive"))
    )
    (net (code "201") (name "/V_OUT201") (class "Default")
      (node (ref "P_O_3") (pin "15") (pinfunction "15_15") (pintype "passive"))
    )
    (net (code "202") (name "/V_OUT202") (class "Default")
      (node (ref "P_O_3") (pin "13") (pinfunction "13_13") (pintype "passive"))
    )
    (net (code "203") (name "/V_OUT203") (class "Default")
      (node (ref "P_O_3") (pin "14") (pinfunction "14_14") (pintype "passive"))
    )
    (net (code "204") (name "/V_OUT204") (class "Default")
      (node (ref "P_O_3") (pin "16") (pinfunction "16_16") (pintype "passive"))
    )
    (net (code "205") (name "/V_OUT205") (class "Default")
      (node (ref "P_O_3") (pin "19") (pinfunction "19_19") (pintype "passive"))
    )
    (net (code "206") (name "/V_OUT206") (class "Default")
      (node (ref "P_O_3") (pin "17") (pinfunction "17_17") (pintype "passive"))
    )
    (net (code "207") (name "/V_OUT207") (class "Default")
      (node (ref "P_O_3") (pin "18") (pinfunction "18_18") (pintype "passive"))
    )
    (net (code "208") (name "/V_OUT208") (class "Default")
      (node (ref "P_O_3") (pin "20") (pinfunction "20_20") (pintype "passive"))
    )
    (net (code "209") (name "/V_OUT209") (class "Default")
      (node (ref "P_O_3") (pin "23") (pinfunction "23_23") (pintype "passive"))
    )
    (net (code "210") (name "/V_OUT210") (class "Default")
      (node (ref "P_O_3") (pin "21") (pinfunction "21_21") (pintype "passive"))
    )
    (net (code "211") (name "/V_OUT211") (class "Default")
      (node (ref "P_O_3") (pin "22") (pinfunction "22_22") (pintype "passive"))
    )
    (net (code "212") (name "/V_OUT212") (class "Default")
      (node (ref "P_O_3") (pin "24") (pinfunction "24_24") (pintype "passive"))
    )
    (net (code "213") (name "/V_OUT213") (class "Default")
      (node (ref "P_O_3") (pin "27") (pinfunction "27_27") (pintype "passive"))
    )
    (net (code "214") (name "/V_OUT214") (class "Default")
      (node (ref "P_O_3") (pin "25") (pinfunction "25_25") (pintype "passive"))
    )
    (net (code "215") (name "/V_OUT215") (class "Default")
      (node (ref "P_O_3") (pin "26") (pinfunction "26_26") (pintype "passive"))
    )
    (net (code "216") (name "/V_OUT216") (class "Default")
      (node (ref "P_O_3") (pin "28") (pinfunction "28_28") (pintype "passive"))
    )
    (net (code "217") (name "/V_OUT217") (class "Default")
      (node (ref "P_O_3") (pin "31") (pinfunction "31_31") (pintype "passive"))
    )
    (net (code "218") (name "/V_OUT218") (class "Default")
      (node (ref "P_O_3") (pin "29") (pinfunction "29_29") (pintype "passive"))
    )
    (net (code "219") (name "/V_OUT219") (class "Default")
      (node (ref "P_O_3") (pin "30") (pinfunction "30_30") (pintype "passive"))
    )
    (net (code "220") (name "/V_OUT220") (class "Default")
      (node (ref "P_O_3") (pin "32") (pinfunction "32_32") (pintype "passive"))
    )
    (net (code "221") (name "/V_OUT221") (class "Default")
      (node (ref "P_O_3") (pin "35") (pinfunction "35_35") (pintype "passive"))
    )
    (net (code "222") (name "/V_OUT222") (class "Default")
      (node (ref "P_O_3") (pin "33") (pinfunction "33_33") (pintype "passive"))
    )
    (net (code "223") (name "/V_OUT223") (class "Default")
      (node (ref "P_O_3") (pin "34") (pinfunction "34_34") (pintype "passive"))
    )
    (net (code "224") (name "/V_OUT224") (class "Default")
      (node (ref "P_O_3") (pin "36") (pinfunction "36_36") (pintype "passive"))
    )
    (net (code "225") (name "/V_OUT225") (class "Default")
      (node (ref "P_O_3") (pin "37") (pinfunction "37_37") (pintype "passive"))
    )
    (net (code "226") (name "/V_OUT226") (class "Default")
      (node (ref "P_E_4") (pin "2") (pinfunction "2_2") (pintype "passive"))
    )
    (net (code "227") (name "/V_OUT227") (class "Default")
      (node (ref "P_E_4") (pin "4") (pinfunction "4_4") (pintype "passive"))
    )
    (net (code "228") (name "/V_OUT228") (class "Default")
      (node (ref "P_E_4") (pin "3") (pinfunction "3_3") (pintype "passive"))
    )
    (net (code "229") (name "/V_OUT229") (class "Default")
      (node (ref "P_E_4") (pin "1") (pinfunction "1_1") (pintype "passive"))
    )
    (net (code "230") (name "/V_OUT230") (class "Default")
      (node (ref "P_E_4") (pin "6") (pinfunction "6_6") (pintype "passive"))
    )
    (net (code "231") (name "/V_OUT231") (class "Default")
      (node (ref "P_E_4") (pin "8") (pinfunction "8_8") (pintype "passive"))
    )
    (net (code "232") (name "/V_OUT232") (class "Default")
      (node (ref "P_E_4") (pin "7") (pinfunction "7_7") (pintype "passive"))
    )
    (net (code "233") (name "/V_OUT233") (class "Default")
      (node (ref "P_E_4") (pin "5") (pinfunction "5_5") (pintype "passive"))
    )
    (net (code "234") (name "/V_OUT234") (class "Default")
      (node (ref "P_E_4") (pin "10") (pinfunction "10_10") (pintype "passive"))
    )
    (net (code "235") (name "/V_OUT235") (class "Default")
      (node (ref "P_E_4") (pin "12") (pinfunction "12_12") (pintype "passive"))
    )
    (net (code "236") (name "/V_OUT236") (class "Default")
      (node (ref "P_E_4") (pin "11") (pinfunction "11_11") (pintype "passive"))
    )
    (net (code "237") (name "/V_OUT237") (class "Default")
      (node (ref "P_E_4") (pin "9") (pinfunction "9_9") (pintype "passive"))
    )
    (net (code "238") (name "/V_OUT238") (class "Default")
      (node (ref "P_E_4") (pin "14") (pinfunction "14_14") (pintype "passive"))
    )
    (net (code "239") (name "/V_OUT239") (class "Default")
      (node (ref "P_E_4") (pin "16") (pinfunction "16_16") (pintype "passive"))
    )
    (net (code "240") (name "/V_OUT240") (class "Default")
      (node (ref "P_E_4") (pin "15") (pinfunction "15_15") (pintype "passive"))
    )
    (net (code "241") (name "/V_OUT241") (class "Default")
      (node (ref "P_E_4") (pin "13") (pinfunction "13_13") (pintype "passive"))
    )
    (net (code "242") (name "/V_OUT242") (class "Default")
      (node (ref "P_E_4") (pin "18") (pinfunction "18_18") (pintype "passive"))
    )
    (net (code "243") (name "/V_OUT243") (class "Default")
      (node (ref "P_E_4") (pin "20") (pinfunction "20_20") (pintype "passive"))
    )
    (net (code "244") (name "/V_OUT244") (class "Default")
      (node (ref "P_E_4") (pin "19") (pinfunction "19_19") (pintype "passive"))
    )
    (net (code "245") (name "/V_OUT245") (class "Default")
      (node (ref "P_E_4") (pin "17") (pinfunction "17_17") (pintype "passive"))
    )
    (net (code "246") (name "/V_OUT246") (class "Default")
      (node (ref "P_E_4") (pin "22") (pinfunction "22_22") (pintype "passive"))
    )
    (net (code "247") (name "/V_OUT247") (class "Default")
      (node (ref "P_E_4") (pin "24") (pinfunction "24_24") (pintype "passive"))
    )
    (net (code "248") (name "/V_OUT248") (class "Default")
      (node (ref "P_E_4") (pin "23") (pinfunction "23_23") (pintype "passive"))
    )
    (net (code "249") (name "/V_OUT249") (class "Default")
      (node (ref "P_E_4") (pin "21") (pinfunction "21_21") (pintype "passive"))
    )
    (net (code "250") (name "/V_OUT250") (class "Default")
      (node (ref "P_E_4") (pin "26") (pinfunction "26_26") (pintype "passive"))
    )
    (net (code "251") (name "/V_OUT251") (class "Default")
      (node (ref "P_E_4") (pin "28") (pinfunction "28_28") (pintype "passive"))
    )
    (net (code "252") (name "/V_OUT252") (class "Default")
      (node (ref "P_E_4") (pin "27") (pinfunction "27_27") (pintype "passive"))
    )
    (net (code "253") (name "/V_OUT253") (class "Default")
      (node (ref "P_E_4") (pin "25") (pinfunction "25_25") (pintype "passive"))
    )
    (net (code "254") (name "/V_OUT254") (class "Default")
      (node (ref "P_E_4") (pin "30") (pinfunction "30_30") (pintype "passive"))
    )
    (net (code "255") (name "/V_OUT255") (class "Default")
      (node (ref "P_E_4") (pin "32") (pinfunction "32_32") (pintype "passive"))
    )
    (net (code "256") (name "/V_OUT256") (class "Default")
      (node (ref "P_E_4") (pin "31") (pinfunction "31_31") (pintype "passive"))
    )
    (net (code "257") (name "/V_OUT257") (class "Default")
      (node (ref "P_E_4") (pin "29") (pinfunction "29_29") (pintype "passive"))
    )
    (net (code "258") (name "/V_OUT258") (class "Default")
      (node (ref "P_E_4") (pin "34") (pinfunction "34_34") (pintype "passive"))
    )
    (net (code "259") (name "/V_OUT259") (class "Default")
      (node (ref "P_E_4") (pin "36") (pinfunction "36_36") (pintype "passive"))
    )
    (net (code "260") (name "/V_OUT260") (class "Default")
      (node (ref "P_E_4") (pin "35") (pinfunction "35_35") (pintype "passive"))
    )
    (net (code "261") (name "/V_OUT261") (class "Default")
      (node (ref "P_E_4") (pin "33") (pinfunction "33_33") (pintype "passive"))
    )
    (net (code "262") (name "/V_OUT262") (class "Default")
      (node (ref "P_E_4") (pin "38") (pinfunction "38_38") (pintype "passive"))
    )
    (net (code "263") (name "/V_OUT263") (class "Default")
      (node (ref "P_E_4") (pin "37") (pinfunction "37_37") (pintype "passive"))
    )
    (net (code "264") (name "/V_OUT264") (class "Default")
      (node (ref "P_O_4") (pin "3") (pinfunction "3_3") (pintype "passive"))
    )
    (net (code "265") (name "/V_OUT265") (class "Default")
      (node (ref "P_O_4") (pin "1") (pinfunction "1_1") (pintype "passive"))
    )
    (net (code "266") (name "/V_OUT266") (class "Default")
      (node (ref "P_O_4") (pin "2") (pinfunction "2_2") (pintype "passive"))
    )
    (net (code "267") (name "/V_OUT267") (class "Default")
      (node (ref "P_O_4") (pin "4") (pinfunction "4_4") (pintype "passive"))
    )
    (net (code "268") (name "/V_OUT268") (class "Default")
      (node (ref "P_O_4") (pin "7") (pinfunction "7_7") (pintype "passive"))
    )
    (net (code "269") (name "/V_OUT269") (class "Default")
      (node (ref "P_O_4") (pin "5") (pinfunction "5_5") (pintype "passive"))
    )
    (net (code "270") (name "/V_OUT270") (class "Default")
      (node (ref "P_O_4") (pin "6") (pinfunction "6_6") (pintype "passive"))
    )
    (net (code "271") (name "/V_OUT271") (class "Default")
      (node (ref "P_O_4") (pin "8") (pinfunction "8_8") (pintype "passive"))
    )
    (net (code "272") (name "/V_OUT272") (class "Default")
      (node (ref "P_O_4") (pin "11") (pinfunction "11_11") (pintype "passive"))
    )
    (net (code "273") (name "/V_OUT273") (class "Default")
      (node (ref "P_O_4") (pin "9") (pinfunction "9_9") (pintype "passive"))
    )
    (net (code "274") (name "/V_OUT274") (class "Default")
      (node (ref "P_O_4") (pin "10") (pinfunction "10_10") (pintype "passive"))
    )
    (net (code "275") (name "/V_OUT275") (class "Default")
      (node (ref "P_O_4") (pin "12") (pinfunction "12_12") (pintype "passive"))
    )
    (net (code "276") (name "/V_OUT276") (class "Default")
      (node (ref "P_O_4") (pin "15") (pinfunction "15_15") (pintype "passive"))
    )
    (net (code "277") (name "/V_OUT277") (class "Default")
      (node (ref "P_O_4") (pin "13") (pinfunction "13_13") (pintype "passive"))
    )
    (net (code "278") (name "/V_OUT278") (class "Default")
      (node (ref "P_O_4") (pin "14") (pinfunction "14_14") (pintype "passive"))
    )
    (net (code "279") (name "/V_OUT279") (class "Default")
      (node (ref "P_O_4") (pin "16") (pinfunction "16_16") (pintype "passive"))
    )
    (net (code "280") (name "/V_OUT280") (class "Default")
      (node (ref "P_O_4") (pin "19") (pinfunction "19_19") (pintype "passive"))
    )
    (net (code "281") (name "/V_OUT281") (class "Default")
      (node (ref "P_O_4") (pin "17") (pinfunction "17_17") (pintype "passive"))
    )
    (net (code "282") (name "/V_OUT282") (class "Default")
      (node (ref "P_O_4") (pin "18") (pinfunction "18_18") (pintype "passive"))
    )
    (net (code "283") (name "/V_OUT283") (class "Default")
      (node (ref "P_O_4") (pin "20") (pinfunction "20_20") (pintype "passive"))
    )
    (net (code "284") (name "/V_OUT284") (class "Default")
      (node (ref "P_O_4") (pin "23") (pinfunction "23_23") (pintype "passive"))
    )
    (net (code "285") (name "/V_OUT285") (class "Default")
      (node (ref "P_O_4") (pin "21") (pinfunction "21_21") (pintype "passive"))
    )
    (net (code "286") (name "/V_OUT286") (class "Default")
      (node (ref "P_O_4") (pin "22") (pinfunction "22_22") (pintype "passive"))
    )
    (net (code "287") (name "/V_OUT287") (class "Default")
      (node (ref "P_O_4") (pin "24") (pinfunction "24_24") (pintype "passive"))
    )
    (net (code "288") (name "/V_OUT288") (class "Default")
      (node (ref "P_O_4") (pin "27") (pinfunction "27_27") (pintype "passive"))
    )
    (net (code "289") (name "/V_OUT289") (class "Default")
      (node (ref "P_O_4") (pin "25") (pinfunction "25_25") (pintype "passive"))
    )
    (net (code "290") (name "/V_OUT290") (class "Default")
      (node (ref "P_O_4") (pin "26") (pinfunction "26_26") (pintype "passive"))
    )
    (net (code "291") (name "/V_OUT291") (class "Default")
      (node (ref "P_O_4") (pin "28") (pinfunction "28_28") (pintype "passive"))
    )
    (net (code "292") (name "/V_OUT292") (class "Default")
      (node (ref "P_O_4") (pin "31") (pinfunction "31_31") (pintype "passive"))
    )
    (net (code "293") (name "/V_OUT293") (class "Default")
      (node (ref "P_O_4") (pin "29") (pinfunction "29_29") (pintype "passive"))
    )
    (net (code "294") (name "/V_OUT294") (class "Default")
      (node (ref "P_O_4") (pin "30") (pinfunction "30_30") (pintype "passive"))
    )
    (net (code "295") (name "/V_OUT295") (class "Default")
      (node (ref "P_O_4") (pin "32") (pinfunction "32_32") (pintype "passive"))
    )
    (net (code "296") (name "/V_OUT296") (class "Default")
      (node (ref "P_O_4") (pin "35") (pinfunction "35_35") (pintype "passive"))
    )
    (net (code "297") (name "/V_OUT297") (class "Default")
      (node (ref "P_O_4") (pin "33") (pinfunction "33_33") (pintype "passive"))
    )
    (net (code "298") (name "/V_OUT298") (class "Default")
      (node (ref "P_O_4") (pin "34") (pinfunction "34_34") (pintype "passive"))
    )
    (net (code "299") (name "/V_OUT299") (class "Default")
      (node (ref "P_O_4") (pin "36") (pinfunction "36_36") (pintype "passive"))
    )
    (net (code "300") (name "/V_OUT300") (class "Default")
      (node (ref "P_O_4") (pin "37") (pinfunction "37_37") (pintype "passive"))
    )
    (net (code "302") (name "GND") (class "Default")
      (node (ref "P_E_1") (pin "39") (pinfunction "39_39") (pintype "passive"))
      (node (ref "P_E_1") (pin "40") (pinfunction "40_40") (pintype "passive"))
      (node (ref "P_E_2") (pin "39") (pinfunction "39_39") (pintype "passive"))
      (node (ref "P_E_2") (pin "40") (pinfunction "40_40") (pintype "passive"))
      (node (ref "P_E_3") (pin "39") (pinfunction "39_39") (pintype "passive"))
      (node (ref "P_E_3") (pin "40") (pinfunction "40_40") (pintype "passive"))
      (node (ref "P_E_4") (pin "39") (pinfunction "39_39") (pintype "passive"))
      (node (ref "P_E_4") (pin "40") (pinfunction "40_40") (pintype "passive"))
      (node (ref "P_O_1") (pin "38") (pinfunction "38_38") (pintype "passive"))
      (node (ref "P_O_1") (pin "39") (pinfunction "39_39") (pintype "passive"))
      (node (ref "P_O_1") (pin "40") (pinfunction "40_40") (pintype "passive"))
      (node (ref "P_O_2") (pin "38") (pinfunction "38_38") (pintype "passive"))
      (node (ref "P_O_2") (pin "39") (pinfunction "39_39") (pintype "passive"))
      (node (ref "P_O_2") (pin "40") (pinfunction "40_40") (pintype "passive"))
      (node (ref "P_O_3") (pin "38") (pinfunction "38_38") (pintype "passive"))
      (node (ref "P_O_3") (pin "39") (pinfunction "39_39") (pintype "passive"))
      (node (ref "P_O_3") (pin "40") (pinfunction "40_40") (pintype "passive"))
      (node (ref "P_O_4") (pin "38") (pinfunction "38_38") (pintype "passive"))
      (node (ref "P_O_4") (pin "39") (pinfunction "39_39") (pintype "passive"))
      (node (ref "P_O_4") (pin "40") (pinfunction "40_40") (pintype "passive"))
    )
  )
)
